# CM4_Conn.net
KiCad netlist of a schematic drawn in Altium Designer
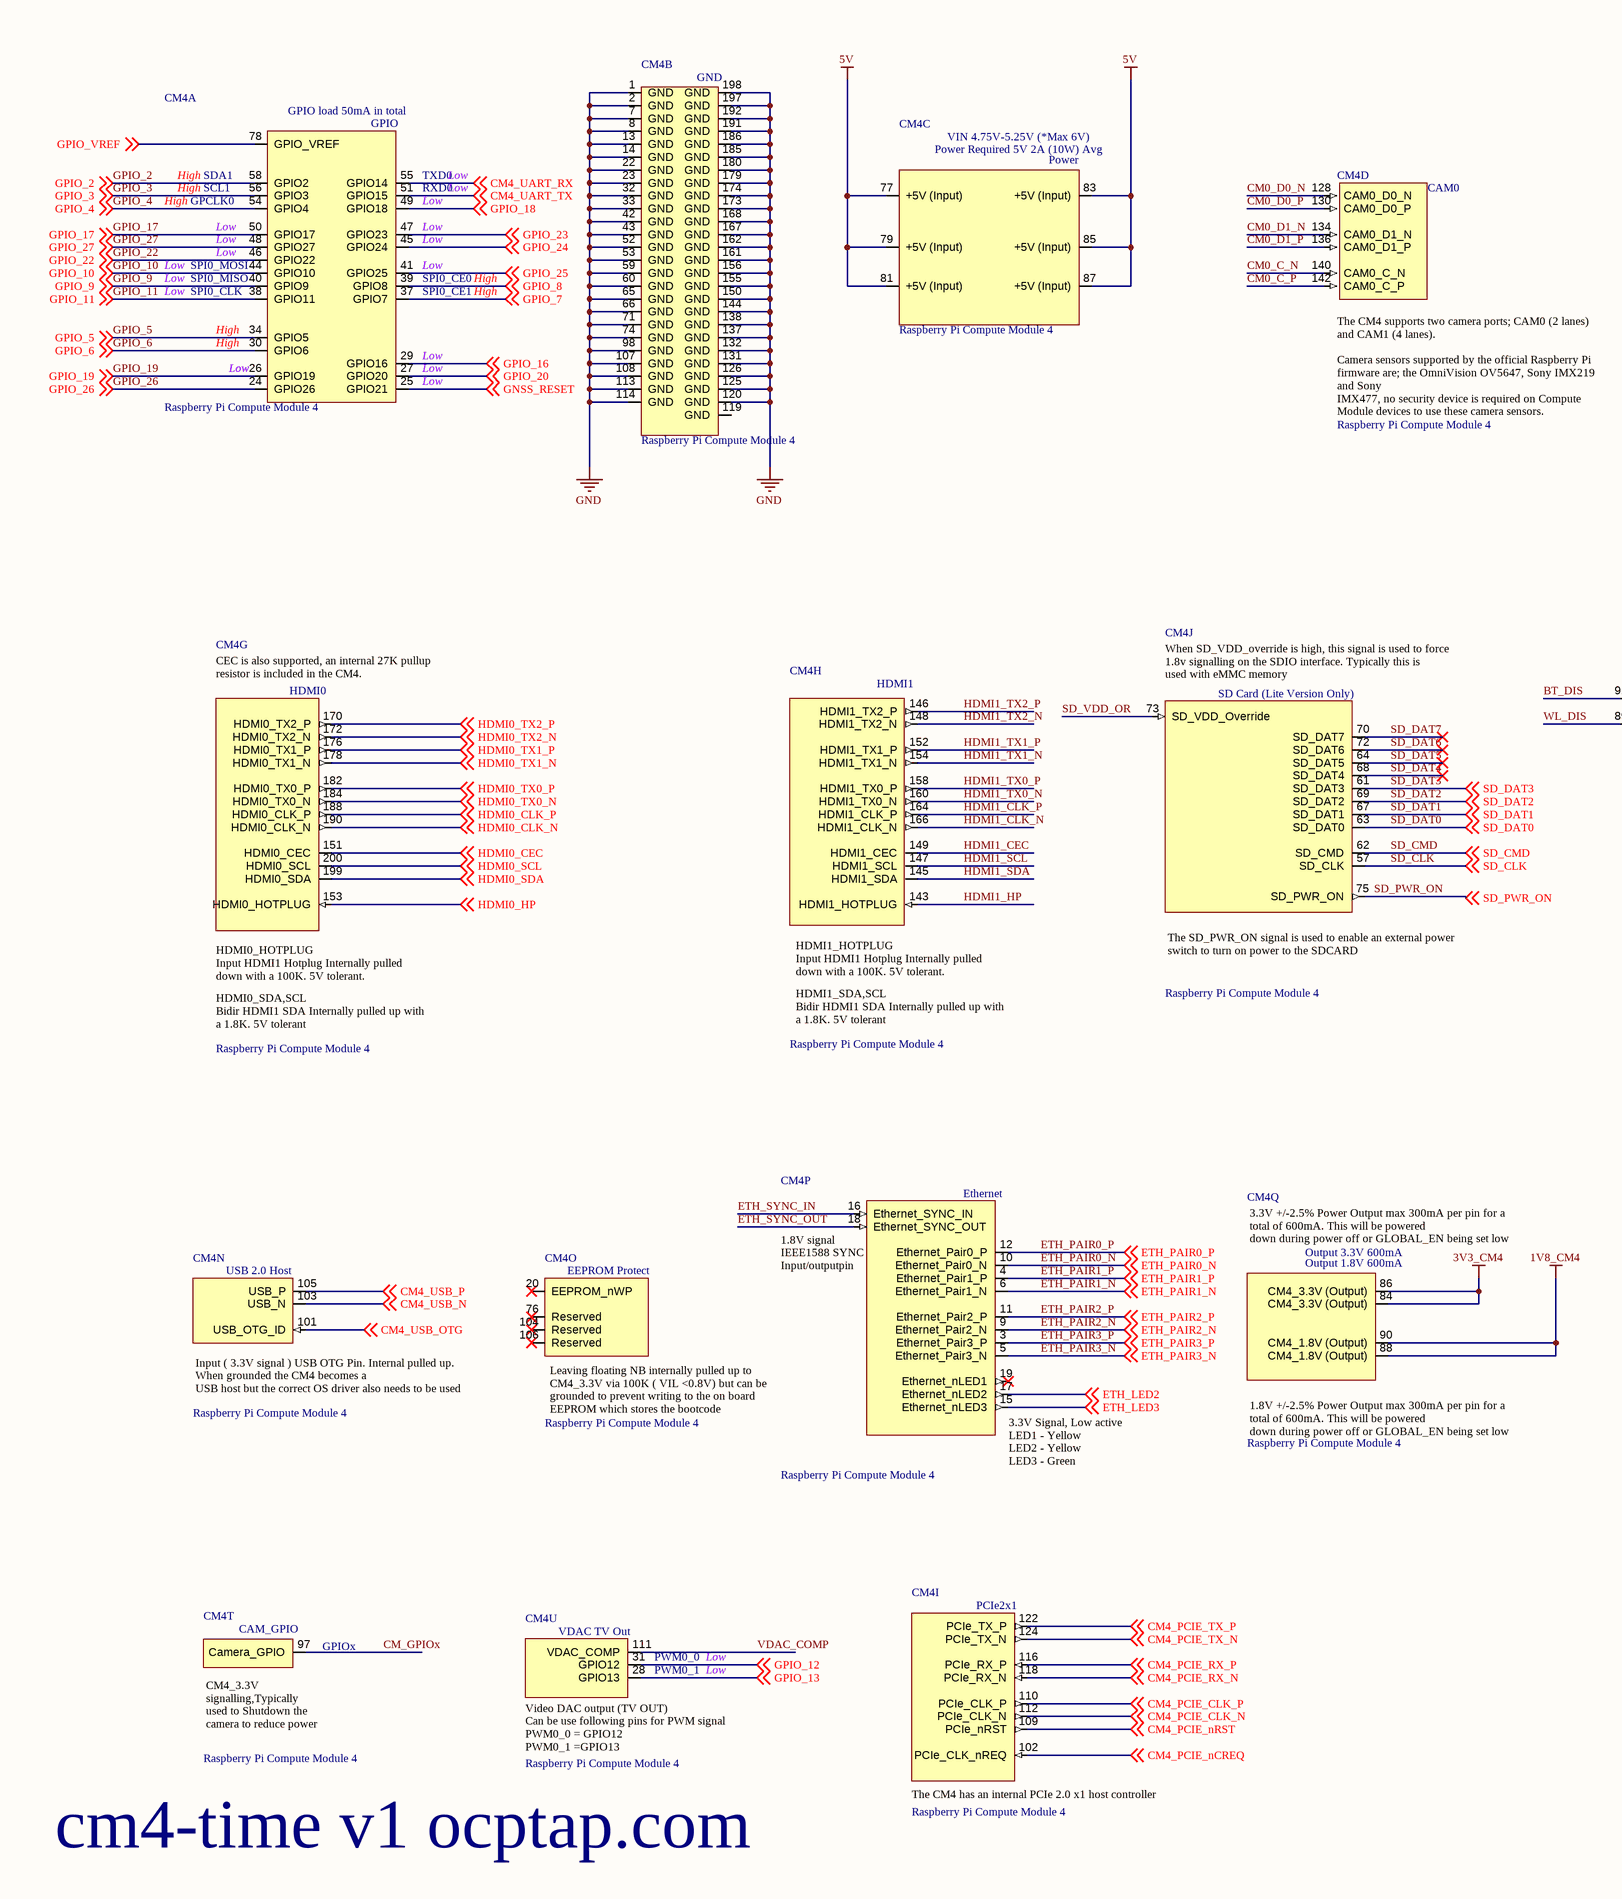
[diagram p0: CM4_Conn.SchDoc, left]
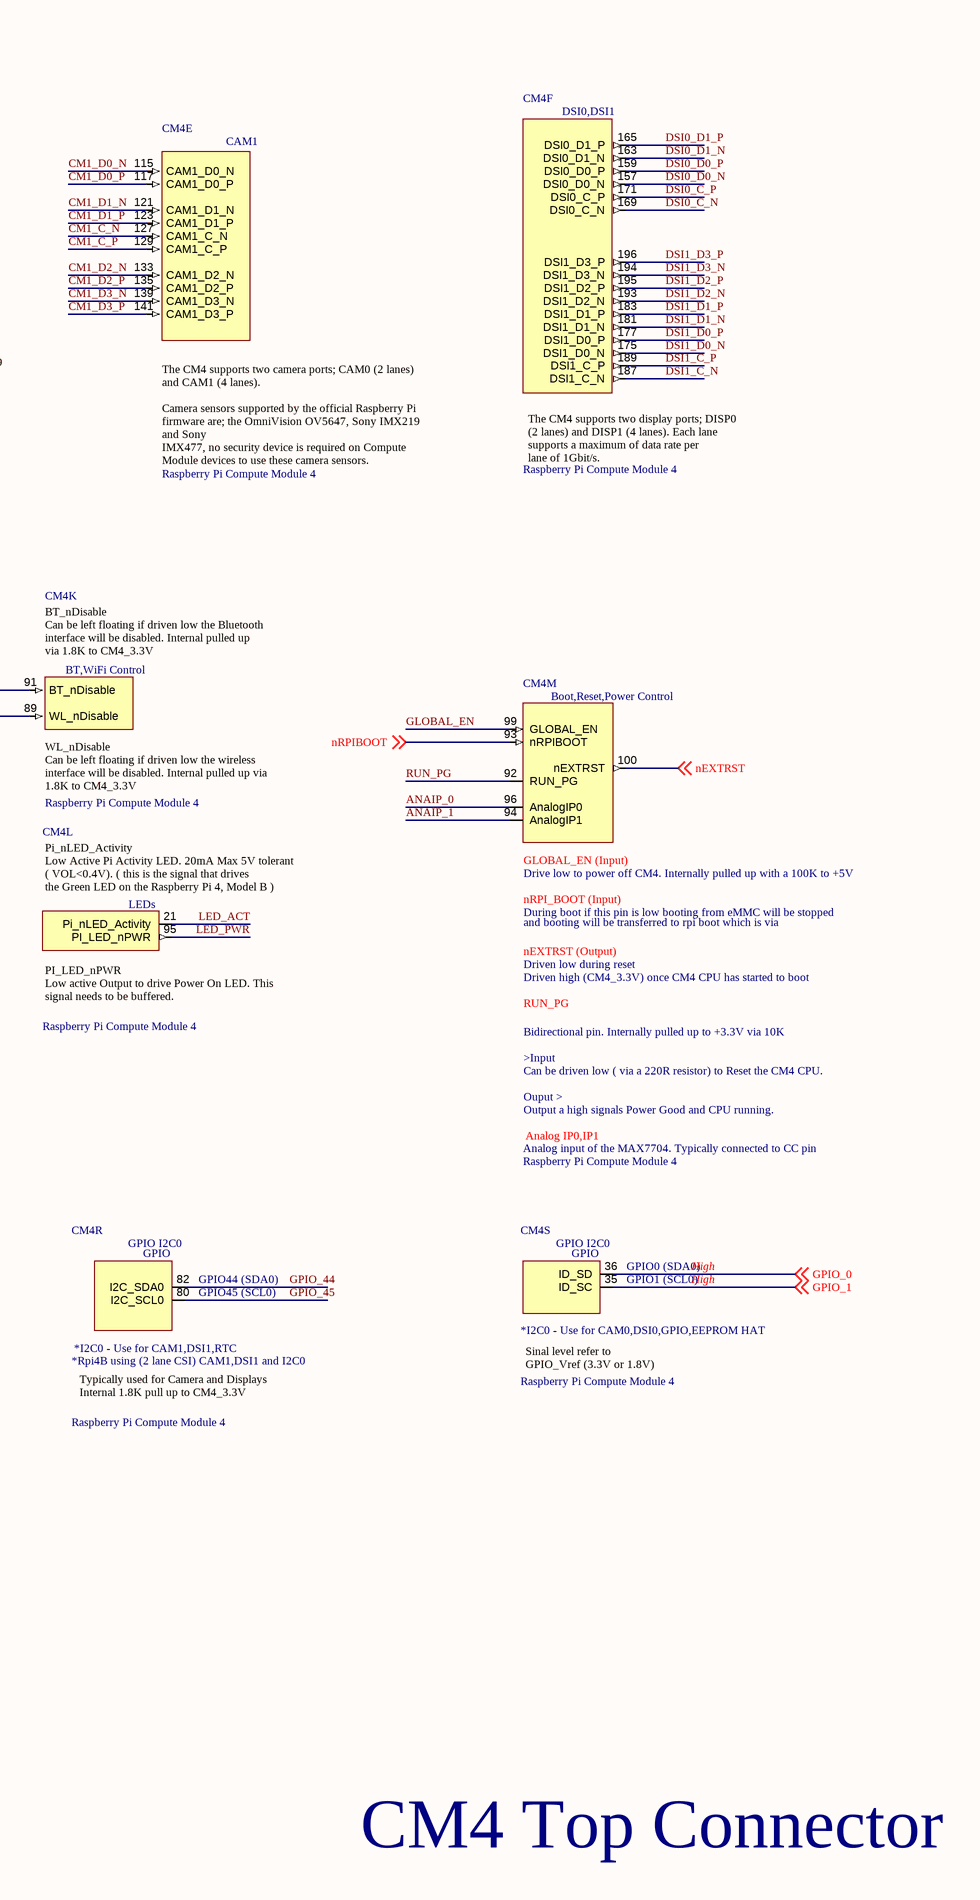
[diagram p1: CM4_Conn.SchDoc, right]

(export (version "E")
  (design (tool "Eeschema 10.0.6"))
  (components
    (comp (ref "CM4")
      (value "Raspberry Pi Compute Module 4")
      (footprint "CM4-F40C-100DS-0.4v_1.5mm_0mm")
      (description "Raspberry Pi Compute Module 4 by Amornthep Phunsin")
      (libsource (lib "CM4") (part "CM4"))
    )
  )
  (nets
    (net (code "1") (name "/ANAIP_0") (class "Default")
      (node (ref "CM4") (pin "96") (pinfunction "AnalogIP0_96") (pintype "passive"))
    )
    (net (code "2") (name "/ANAIP_1") (class "Default")
      (node (ref "CM4") (pin "94") (pinfunction "AnalogIP1_94") (pintype "passive"))
    )
    (net (code "3") (name "/BT_DIS") (class "Default")
      (node (ref "CM4") (pin "91") (pinfunction "BT_nDisable_91") (pintype "input"))
    )
    (net (code "4") (name "/CM0_C_N") (class "Default")
      (node (ref "CM4") (pin "140") (pinfunction "CAM0_C_N_140") (pintype "input"))
    )
    (net (code "5") (name "/CM0_C_P") (class "Default")
      (node (ref "CM4") (pin "142") (pinfunction "CAM0_C_P_142") (pintype "input"))
    )
    (net (code "6") (name "/CM0_D0_N") (class "Default")
      (node (ref "CM4") (pin "128") (pinfunction "CAM0_D0_N_128") (pintype "input"))
    )
    (net (code "7") (name "/CM0_D0_P") (class "Default")
      (node (ref "CM4") (pin "130") (pinfunction "CAM0_D0_P_130") (pintype "input"))
    )
    (net (code "8") (name "/CM0_D1_N") (class "Default")
      (node (ref "CM4") (pin "134") (pinfunction "CAM0_D1_N_134") (pintype "input"))
    )
    (net (code "9") (name "/CM0_D1_P") (class "Default")
      (node (ref "CM4") (pin "136") (pinfunction "CAM0_D1_P_136") (pintype "input"))
    )
    (net (code "10") (name "/CM1_C_N") (class "Default")
      (node (ref "CM4") (pin "127") (pinfunction "CAM1_C_N_127") (pintype "input"))
    )
    (net (code "11") (name "/CM1_C_P") (class "Default")
      (node (ref "CM4") (pin "129") (pinfunction "CAM1_C_P_129") (pintype "input"))
    )
    (net (code "12") (name "/CM1_D0_N") (class "Default")
      (node (ref "CM4") (pin "115") (pinfunction "CAM1_D0_N_115") (pintype "input"))
    )
    (net (code "13") (name "/CM1_D0_P") (class "Default")
      (node (ref "CM4") (pin "117") (pinfunction "CAM1_D0_P_117") (pintype "input"))
    )
    (net (code "14") (name "/CM1_D1_N") (class "Default")
      (node (ref "CM4") (pin "121") (pinfunction "CAM1_D1_N_121") (pintype "input"))
    )
    (net (code "15") (name "/CM1_D1_P") (class "Default")
      (node (ref "CM4") (pin "123") (pinfunction "CAM1_D1_P_123") (pintype "input"))
    )
    (net (code "16") (name "/CM1_D2_N") (class "Default")
      (node (ref "CM4") (pin "133") (pinfunction "CAM1_D2_N_133") (pintype "input"))
    )
    (net (code "17") (name "/CM1_D2_P") (class "Default")
      (node (ref "CM4") (pin "135") (pinfunction "CAM1_D2_P_135") (pintype "input"))
    )
    (net (code "18") (name "/CM1_D3_N") (class "Default")
      (node (ref "CM4") (pin "139") (pinfunction "CAM1_D3_N_139") (pintype "input"))
    )
    (net (code "19") (name "/CM1_D3_P") (class "Default")
      (node (ref "CM4") (pin "141") (pinfunction "CAM1_D3_P_141") (pintype "input"))
    )
    (net (code "20") (name "/CM_GPIOx") (class "Default")
      (node (ref "CM4") (pin "97") (pinfunction "Camera_GPIO_97") (pintype "passive"))
    )
    (net (code "21") (name "/DSI0_C_N") (class "Default")
      (node (ref "CM4") (pin "169") (pinfunction "DSI0_C_N_169") (pintype "output"))
    )
    (net (code "22") (name "/DSI0_C_P") (class "Default")
      (node (ref "CM4") (pin "171") (pinfunction "DSI0_C_P_171") (pintype "output"))
    )
    (net (code "23") (name "/DSI0_D0_N") (class "Default")
      (node (ref "CM4") (pin "157") (pinfunction "DSI0_D0_N_157") (pintype "output"))
    )
    (net (code "24") (name "/DSI0_D0_P") (class "Default")
      (node (ref "CM4") (pin "159") (pinfunction "DSI0_D0_P_159") (pintype "output"))
    )
    (net (code "25") (name "/DSI0_D1_N") (class "Default")
      (node (ref "CM4") (pin "163") (pinfunction "DSI0_D1_N_163") (pintype "output"))
    )
    (net (code "26") (name "/DSI0_D1_P") (class "Default")
      (node (ref "CM4") (pin "165") (pinfunction "DSI0_D1_P_165") (pintype "output"))
    )
    (net (code "27") (name "/DSI1_C_N") (class "Default")
      (node (ref "CM4") (pin "187") (pinfunction "DSI1_C_N_187") (pintype "output"))
    )
    (net (code "28") (name "/DSI1_C_P") (class "Default")
      (node (ref "CM4") (pin "189") (pinfunction "DSI1_C_P_189") (pintype "output"))
    )
    (net (code "29") (name "/DSI1_D0_N") (class "Default")
      (node (ref "CM4") (pin "175") (pinfunction "DSI1_D0_N_175") (pintype "output"))
    )
    (net (code "30") (name "/DSI1_D0_P") (class "Default")
      (node (ref "CM4") (pin "177") (pinfunction "DSI1_D0_P_177") (pintype "output"))
    )
    (net (code "31") (name "/DSI1_D1_N") (class "Default")
      (node (ref "CM4") (pin "181") (pinfunction "DSI1_D1_N_181") (pintype "output"))
    )
    (net (code "32") (name "/DSI1_D1_P") (class "Default")
      (node (ref "CM4") (pin "183") (pinfunction "DSI1_D1_P_183") (pintype "output"))
    )
    (net (code "33") (name "/DSI1_D2_N") (class "Default")
      (node (ref "CM4") (pin "193") (pinfunction "DSI1_D2_N_193") (pintype "output"))
    )
    (net (code "34") (name "/DSI1_D2_P") (class "Default")
      (node (ref "CM4") (pin "195") (pinfunction "DSI1_D2_P_195") (pintype "output"))
    )
    (net (code "35") (name "/DSI1_D3_N") (class "Default")
      (node (ref "CM4") (pin "194") (pinfunction "DSI1_D3_N_194") (pintype "output"))
    )
    (net (code "36") (name "/DSI1_D3_P") (class "Default")
      (node (ref "CM4") (pin "196") (pinfunction "DSI1_D3_P_196") (pintype "output"))
    )
    (net (code "37") (name "/ETH_SYNC_IN") (class "Default")
      (node (ref "CM4") (pin "16") (pinfunction "Ethernet_SYNC_IN_16") (pintype "input"))
    )
    (net (code "38") (name "/ETH_SYNC_OUT") (class "Default")
      (node (ref "CM4") (pin "18") (pinfunction "Ethernet_SYNC_OUT_18") (pintype "input"))
    )
    (net (code "39") (name "/GLOBAL_EN") (class "Default")
      (node (ref "CM4") (pin "99") (pinfunction "GLOBAL_EN_99") (pintype "input"))
    )
    (net (code "40") (name "/GPIO_44") (class "Default")
      (node (ref "CM4") (pin "82") (pinfunction "I2C_SDA0_82") (pintype "passive"))
    )
    (net (code "41") (name "/GPIO_45") (class "Default")
      (node (ref "CM4") (pin "80") (pinfunction "I2C_SCL0_80") (pintype "passive"))
    )
    (net (code "42") (name "/HDMI1_CEC") (class "Default")
      (node (ref "CM4") (pin "149") (pinfunction "HDMI1_CEC_149") (pintype "open_collector"))
    )
    (net (code "43") (name "/HDMI1_CLK_N") (class "Default")
      (node (ref "CM4") (pin "166") (pinfunction "HDMI1_CLK_N_166") (pintype "output"))
    )
    (net (code "44") (name "/HDMI1_CLK_P") (class "Default")
      (node (ref "CM4") (pin "164") (pinfunction "HDMI1_CLK_P_164") (pintype "output"))
    )
    (net (code "45") (name "/HDMI1_HP") (class "Default")
      (node (ref "CM4") (pin "143") (pinfunction "HDMI1_HOTPLUG_143") (pintype "input"))
    )
    (net (code "46") (name "/HDMI1_SCL") (class "Default")
      (node (ref "CM4") (pin "147") (pinfunction "HDMI1_SCL_147") (pintype "open_collector"))
    )
    (net (code "47") (name "/HDMI1_SDA") (class "Default")
      (node (ref "CM4") (pin "145") (pinfunction "HDMI1_SDA_145") (pintype "bidirectional"))
    )
    (net (code "48") (name "/HDMI1_TX0_N") (class "Default")
      (node (ref "CM4") (pin "160") (pinfunction "HDMI1_TX0_N_160") (pintype "output"))
    )
    (net (code "49") (name "/HDMI1_TX0_P") (class "Default")
      (node (ref "CM4") (pin "158") (pinfunction "HDMI1_TX0_P_158") (pintype "output"))
    )
    (net (code "50") (name "/HDMI1_TX1_N") (class "Default")
      (node (ref "CM4") (pin "154") (pinfunction "HDMI1_TX1_N_154") (pintype "output"))
    )
    (net (code "51") (name "/HDMI1_TX1_P") (class "Default")
      (node (ref "CM4") (pin "152") (pinfunction "HDMI1_TX1_P_152") (pintype "output"))
    )
    (net (code "52") (name "/HDMI1_TX2_N") (class "Default")
      (node (ref "CM4") (pin "148") (pinfunction "HDMI1_TX2_N_148") (pintype "output"))
    )
    (net (code "53") (name "/HDMI1_TX2_P") (class "Default")
      (node (ref "CM4") (pin "146") (pinfunction "HDMI1_TX2_P_146") (pintype "output"))
    )
    (net (code "54") (name "/LED_ACT") (class "Default")
      (node (ref "CM4") (pin "21") (pinfunction "Pi_nLED_Activity_21") (pintype "open_collector"))
    )
    (net (code "55") (name "/LED_PWR") (class "Default")
      (node (ref "CM4") (pin "95") (pinfunction "PI_LED_nPWR_95") (pintype "output"))
    )
    (net (code "56") (name "/RUN_PG") (class "Default")
      (node (ref "CM4") (pin "92") (pinfunction "RUN_PG_92") (pintype "passive"))
    )
    (net (code "57") (name "/SD_DAT4") (class "Default")
      (node (ref "CM4") (pin "68") (pinfunction "SD_DAT4_68") (pintype "passive+no_connect"))
    )
    (net (code "58") (name "/SD_DAT5") (class "Default")
      (node (ref "CM4") (pin "64") (pinfunction "SD_DAT5_64") (pintype "passive+no_connect"))
    )
    (net (code "59") (name "/SD_DAT6") (class "Default")
      (node (ref "CM4") (pin "72") (pinfunction "SD_DAT6_72") (pintype "passive+no_connect"))
    )
    (net (code "60") (name "/SD_DAT7") (class "Default")
      (node (ref "CM4") (pin "70") (pinfunction "SD_DAT7_70") (pintype "passive+no_connect"))
    )
    (net (code "61") (name "/SD_VDD_OR") (class "Default")
      (node (ref "CM4") (pin "73") (pinfunction "SD_VDD_Override_73") (pintype "input"))
    )
    (net (code "62") (name "/VDAC_COMP") (class "Default")
      (node (ref "CM4") (pin "111") (pinfunction "VDAC_COMP_111") (pintype "passive"))
    )
    (net (code "63") (name "/WL_DIS") (class "Default")
      (node (ref "CM4") (pin "89") (pinfunction "WL_nDisable_89") (pintype "input"))
    )
    (net (code "64") (name "1V8_CM4") (class "Default")
      (node (ref "CM4") (pin "88") (pinfunction "CM4_1.8V_(Output)_88") (pintype "power_in"))
      (node (ref "CM4") (pin "90") (pinfunction "CM4_1.8V_(Output)_90") (pintype "power_in"))
    )
    (net (code "65") (name "3V3_CM4") (class "Default")
      (node (ref "CM4") (pin "84") (pinfunction "CM4_3.3V_(Output)_84") (pintype "power_in"))
      (node (ref "CM4") (pin "86") (pinfunction "CM4_3.3V_(Output)_86") (pintype "power_in"))
    )
    (net (code "66") (name "5V") (class "Default")
      (node (ref "CM4") (pin "77") (pinfunction "+5V_(Input)_77") (pintype "power_in"))
      (node (ref "CM4") (pin "79") (pinfunction "+5V_(Input)_79") (pintype "power_in"))
      (node (ref "CM4") (pin "81") (pinfunction "+5V_(Input)_81") (pintype "power_in"))
      (node (ref "CM4") (pin "83") (pinfunction "+5V_(Input)_83") (pintype "power_in"))
      (node (ref "CM4") (pin "85") (pinfunction "+5V_(Input)_85") (pintype "power_in"))
      (node (ref "CM4") (pin "87") (pinfunction "+5V_(Input)_87") (pintype "power_in"))
    )
    (net (code "67") (name "CM4_PCIE_CLK_N") (class "Default")
      (node (ref "CM4") (pin "112") (pinfunction "PCIe_CLK_N_112") (pintype "output"))
    )
    (net (code "68") (name "CM4_PCIE_CLK_P") (class "Default")
      (node (ref "CM4") (pin "110") (pinfunction "PCIe_CLK_P_110") (pintype "output"))
    )
    (net (code "69") (name "CM4_PCIE_RX_N") (class "Default")
      (node (ref "CM4") (pin "118") (pinfunction "PCIe_RX_N_118") (pintype "input"))
    )
    (net (code "70") (name "CM4_PCIE_RX_P") (class "Default")
      (node (ref "CM4") (pin "116") (pinfunction "PCIe_RX_P_116") (pintype "input"))
    )
    (net (code "71") (name "CM4_PCIE_TX_N") (class "Default")
      (node (ref "CM4") (pin "124") (pinfunction "PCIe_TX_N_124") (pintype "output"))
    )
    (net (code "72") (name "CM4_PCIE_TX_P") (class "Default")
      (node (ref "CM4") (pin "122") (pinfunction "PCIe_TX_P_122") (pintype "output"))
    )
    (net (code "73") (name "CM4_PCIE_nCREQ") (class "Default")
      (node (ref "CM4") (pin "102") (pinfunction "PCIe_CLK_nREQ_102") (pintype "input"))
    )
    (net (code "74") (name "CM4_PCIE_nRST") (class "Default")
      (node (ref "CM4") (pin "109") (pinfunction "PCIe_nRST_109") (pintype "output"))
    )
    (net (code "75") (name "CM4_UART_RX") (class "Default")
      (node (ref "CM4") (pin "55") (pinfunction "GPIO14_55") (pintype "passive"))
    )
    (net (code "76") (name "CM4_UART_TX") (class "Default")
      (node (ref "CM4") (pin "51") (pinfunction "GPIO15_51") (pintype "passive"))
    )
    (net (code "77") (name "CM4_USB_N") (class "Default")
      (node (ref "CM4") (pin "103") (pinfunction "USB_N_103") (pintype "passive"))
    )
    (net (code "78") (name "CM4_USB_OTG") (class "Default")
      (node (ref "CM4") (pin "101") (pinfunction "USB_OTG_ID_101") (pintype "input"))
    )
    (net (code "79") (name "CM4_USB_P") (class "Default")
      (node (ref "CM4") (pin "105") (pinfunction "USB_P_105") (pintype "passive"))
    )
    (net (code "80") (name "ETH_LED2") (class "Default")
      (node (ref "CM4") (pin "17") (pinfunction "Ethernet_nLED2_17") (pintype "output"))
    )
    (net (code "81") (name "ETH_LED3") (class "Default")
      (node (ref "CM4") (pin "15") (pinfunction "Ethernet_nLED3_15") (pintype "output"))
    )
    (net (code "82") (name "ETH_PAIR0_N") (class "Default")
      (node (ref "CM4") (pin "10") (pinfunction "Ethernet_Pair0_N_10") (pintype "passive"))
    )
    (net (code "83") (name "ETH_PAIR0_P") (class "Default")
      (node (ref "CM4") (pin "12") (pinfunction "Ethernet_Pair0_P_12") (pintype "passive"))
    )
    (net (code "84") (name "ETH_PAIR1_N") (class "Default")
      (node (ref "CM4") (pin "6") (pinfunction "Ethernet_Pair1_N_6") (pintype "passive"))
    )
    (net (code "85") (name "ETH_PAIR1_P") (class "Default")
      (node (ref "CM4") (pin "4") (pinfunction "Ethernet_Pair1_P_4") (pintype "passive"))
    )
    (net (code "86") (name "ETH_PAIR2_N") (class "Default")
      (node (ref "CM4") (pin "9") (pinfunction "Ethernet_Pair2_N_9") (pintype "passive"))
    )
    (net (code "87") (name "ETH_PAIR2_P") (class "Default")
      (node (ref "CM4") (pin "11") (pinfunction "Ethernet_Pair2_P_11") (pintype "passive"))
    )
    (net (code "88") (name "ETH_PAIR3_N") (class "Default")
      (node (ref "CM4") (pin "5") (pinfunction "Ethernet_Pair3_N_5") (pintype "passive"))
    )
    (net (code "89") (name "ETH_PAIR3_P") (class "Default")
      (node (ref "CM4") (pin "3") (pinfunction "Ethernet_Pair3_P_3") (pintype "passive"))
    )
    (net (code "90") (name "GND") (class "Default")
      (node (ref "CM4") (pin "1") (pinfunction "GND_1") (pintype "power_in"))
      (node (ref "CM4") (pin "107") (pinfunction "GND_107") (pintype "power_in"))
      (node (ref "CM4") (pin "108") (pinfunction "GND_108") (pintype "power_in"))
      (node (ref "CM4") (pin "113") (pinfunction "GND_113") (pintype "power_in"))
      (node (ref "CM4") (pin "114") (pinfunction "GND_114") (pintype "power_in"))
      (node (ref "CM4") (pin "120") (pinfunction "GND_120") (pintype "power_in"))
      (node (ref "CM4") (pin "125") (pinfunction "GND_125") (pintype "power_in"))
      (node (ref "CM4") (pin "126") (pinfunction "GND_126") (pintype "power_in"))
      (node (ref "CM4") (pin "13") (pinfunction "GND_13") (pintype "power_in"))
      (node (ref "CM4") (pin "131") (pinfunction "GND_131") (pintype "power_in"))
      (node (ref "CM4") (pin "132") (pinfunction "GND_132") (pintype "power_in"))
      (node (ref "CM4") (pin "137") (pinfunction "GND_137") (pintype "power_in"))
      (node (ref "CM4") (pin "138") (pinfunction "GND_138") (pintype "power_in"))
      (node (ref "CM4") (pin "14") (pinfunction "GND_14") (pintype "power_in"))
      (node (ref "CM4") (pin "144") (pinfunction "GND_144") (pintype "power_in"))
      (node (ref "CM4") (pin "150") (pinfunction "GND_150") (pintype "power_in"))
      (node (ref "CM4") (pin "155") (pinfunction "GND_155") (pintype "power_in"))
      (node (ref "CM4") (pin "156") (pinfunction "GND_156") (pintype "power_in"))
      (node (ref "CM4") (pin "161") (pinfunction "GND_161") (pintype "power_in"))
      (node (ref "CM4") (pin "162") (pinfunction "GND_162") (pintype "power_in"))
      (node (ref "CM4") (pin "167") (pinfunction "GND_167") (pintype "power_in"))
      (node (ref "CM4") (pin "168") (pinfunction "GND_168") (pintype "power_in"))
      (node (ref "CM4") (pin "173") (pinfunction "GND_173") (pintype "power_in"))
      (node (ref "CM4") (pin "174") (pinfunction "GND_174") (pintype "power_in"))
      (node (ref "CM4") (pin "179") (pinfunction "GND_179") (pintype "power_in"))
      (node (ref "CM4") (pin "180") (pinfunction "GND_180") (pintype "power_in"))
      (node (ref "CM4") (pin "185") (pinfunction "GND_185") (pintype "power_in"))
      (node (ref "CM4") (pin "186") (pinfunction "GND_186") (pintype "power_in"))
      (node (ref "CM4") (pin "191") (pinfunction "GND_191") (pintype "power_in"))
      (node (ref "CM4") (pin "192") (pinfunction "GND_192") (pintype "power_in"))
      (node (ref "CM4") (pin "197") (pinfunction "GND_197") (pintype "power_in"))
      (node (ref "CM4") (pin "198") (pinfunction "GND_198") (pintype "power_in"))
      (node (ref "CM4") (pin "2") (pinfunction "GND_2") (pintype "power_in"))
      (node (ref "CM4") (pin "22") (pinfunction "GND_22") (pintype "power_in"))
      (node (ref "CM4") (pin "23") (pinfunction "GND_23") (pintype "power_in"))
      (node (ref "CM4") (pin "32") (pinfunction "GND_32") (pintype "power_in"))
      (node (ref "CM4") (pin "33") (pinfunction "GND_33") (pintype "power_in"))
      (node (ref "CM4") (pin "42") (pinfunction "GND_42") (pintype "power_in"))
      (node (ref "CM4") (pin "43") (pinfunction "GND_43") (pintype "power_in"))
      (node (ref "CM4") (pin "52") (pinfunction "GND_52") (pintype "power_in"))
      (node (ref "CM4") (pin "53") (pinfunction "GND_53") (pintype "power_in"))
      (node (ref "CM4") (pin "59") (pinfunction "GND_59") (pintype "power_in"))
      (node (ref "CM4") (pin "60") (pinfunction "GND_60") (pintype "power_in"))
      (node (ref "CM4") (pin "65") (pinfunction "GND_65") (pintype "power_in"))
      (node (ref "CM4") (pin "66") (pinfunction "GND_66") (pintype "power_in"))
      (node (ref "CM4") (pin "7") (pinfunction "GND_7") (pintype "power_in"))
      (node (ref "CM4") (pin "71") (pinfunction "GND_71") (pintype "power_in"))
      (node (ref "CM4") (pin "74") (pinfunction "GND_74") (pintype "power_in"))
      (node (ref "CM4") (pin "8") (pinfunction "GND_8") (pintype "power_in"))
      (node (ref "CM4") (pin "98") (pinfunction "GND_98") (pintype "power_in"))
    )
    (net (code "91") (name "GNSS_RESET") (class "Default")
      (node (ref "CM4") (pin "25") (pinfunction "GPIO21_25") (pintype "passive"))
    )
    (net (code "92") (name "GPIO_0") (class "Default")
      (node (ref "CM4") (pin "36") (pinfunction "ID_SD_36") (pintype "passive"))
    )
    (net (code "93") (name "GPIO_1") (class "Default")
      (node (ref "CM4") (pin "35") (pinfunction "ID_SC_35") (pintype "passive"))
    )
    (net (code "94") (name "GPIO_2") (class "Default")
      (node (ref "CM4") (pin "58") (pinfunction "GPIO2_58") (pintype "passive"))
    )
    (net (code "95") (name "GPIO_3") (class "Default")
      (node (ref "CM4") (pin "56") (pinfunction "GPIO3_56") (pintype "passive"))
    )
    (net (code "96") (name "GPIO_4") (class "Default")
      (node (ref "CM4") (pin "54") (pinfunction "GPIO4_54") (pintype "passive"))
    )
    (net (code "97") (name "GPIO_5") (class "Default")
      (node (ref "CM4") (pin "34") (pinfunction "GPIO5_34") (pintype "passive"))
    )
    (net (code "98") (name "GPIO_6") (class "Default")
      (node (ref "CM4") (pin "30") (pinfunction "GPIO6_30") (pintype "passive"))
    )
    (net (code "99") (name "GPIO_7") (class "Default")
      (node (ref "CM4") (pin "37") (pinfunction "GPIO7_37") (pintype "passive"))
    )
    (net (code "100") (name "GPIO_8") (class "Default")
      (node (ref "CM4") (pin "39") (pinfunction "GPIO8_39") (pintype "passive"))
    )
    (net (code "101") (name "GPIO_9") (class "Default")
      (node (ref "CM4") (pin "40") (pinfunction "GPIO9_40") (pintype "passive"))
    )
    (net (code "102") (name "GPIO_10") (class "Default")
      (node (ref "CM4") (pin "44") (pinfunction "GPIO10_44") (pintype "passive"))
    )
    (net (code "103") (name "GPIO_11") (class "Default")
      (node (ref "CM4") (pin "38") (pinfunction "GPIO11_38") (pintype "passive"))
    )
    (net (code "104") (name "GPIO_12") (class "Default")
      (node (ref "CM4") (pin "31") (pinfunction "GPIO12_31") (pintype "passive"))
    )
    (net (code "105") (name "GPIO_13") (class "Default")
      (node (ref "CM4") (pin "28") (pinfunction "GPIO13_28") (pintype "passive"))
    )
    (net (code "106") (name "GPIO_16") (class "Default")
      (node (ref "CM4") (pin "29") (pinfunction "GPIO16_29") (pintype "passive"))
    )
    (net (code "107") (name "GPIO_17") (class "Default")
      (node (ref "CM4") (pin "50") (pinfunction "GPIO17_50") (pintype "passive"))
    )
    (net (code "108") (name "GPIO_18") (class "Default")
      (node (ref "CM4") (pin "49") (pinfunction "GPIO18_49") (pintype "passive"))
    )
    (net (code "109") (name "GPIO_19") (class "Default")
      (node (ref "CM4") (pin "26") (pinfunction "GPIO19_26") (pintype "passive"))
    )
    (net (code "110") (name "GPIO_20") (class "Default")
      (node (ref "CM4") (pin "27") (pinfunction "GPIO20_27") (pintype "passive"))
    )
    (net (code "111") (name "GPIO_22") (class "Default")
      (node (ref "CM4") (pin "46") (pinfunction "GPIO22_46") (pintype "passive"))
    )
    (net (code "112") (name "GPIO_23") (class "Default")
      (node (ref "CM4") (pin "47") (pinfunction "GPIO23_47") (pintype "passive"))
    )
    (net (code "113") (name "GPIO_24") (class "Default")
      (node (ref "CM4") (pin "45") (pinfunction "GPIO24_45") (pintype "passive"))
    )
    (net (code "114") (name "GPIO_25") (class "Default")
      (node (ref "CM4") (pin "41") (pinfunction "GPIO25_41") (pintype "passive"))
    )
    (net (code "115") (name "GPIO_26") (class "Default")
      (node (ref "CM4") (pin "24") (pinfunction "GPIO26_24") (pintype "passive"))
    )
    (net (code "116") (name "GPIO_27") (class "Default")
      (node (ref "CM4") (pin "48") (pinfunction "GPIO27_48") (pintype "passive"))
    )
    (net (code "117") (name "GPIO_VREF") (class "Default")
      (node (ref "CM4") (pin "78") (pinfunction "GPIO_VREF_78") (pintype "power_in"))
    )
    (net (code "118") (name "HDMI0_CEC") (class "Default")
      (node (ref "CM4") (pin "151") (pinfunction "HDMI0_CEC_151") (pintype "open_collector"))
    )
    (net (code "119") (name "HDMI0_CLK_N") (class "Default")
      (node (ref "CM4") (pin "190") (pinfunction "HDMI0_CLK_N_190") (pintype "output"))
    )
    (net (code "120") (name "HDMI0_CLK_P") (class "Default")
      (node (ref "CM4") (pin "188") (pinfunction "HDMI0_CLK_P_188") (pintype "output"))
    )
    (net (code "121") (name "HDMI0_HP") (class "Default")
      (node (ref "CM4") (pin "153") (pinfunction "HDMI0_HOTPLUG_153") (pintype "input"))
    )
    (net (code "122") (name "HDMI0_SCL") (class "Default")
      (node (ref "CM4") (pin "200") (pinfunction "HDMI0_SCL_200") (pintype "open_collector"))
    )
    (net (code "123") (name "HDMI0_SDA") (class "Default")
      (node (ref "CM4") (pin "199") (pinfunction "HDMI0_SDA_199") (pintype "bidirectional"))
    )
    (net (code "124") (name "HDMI0_TX0_N") (class "Default")
      (node (ref "CM4") (pin "184") (pinfunction "HDMI0_TX0_N_184") (pintype "output"))
    )
    (net (code "125") (name "HDMI0_TX0_P") (class "Default")
      (node (ref "CM4") (pin "182") (pinfunction "HDMI0_TX0_P_182") (pintype "output"))
    )
    (net (code "126") (name "HDMI0_TX1_N") (class "Default")
      (node (ref "CM4") (pin "178") (pinfunction "HDMI0_TX1_N_178") (pintype "output"))
    )
    (net (code "127") (name "HDMI0_TX1_P") (class "Default")
      (node (ref "CM4") (pin "176") (pinfunction "HDMI0_TX1_P_176") (pintype "output"))
    )
    (net (code "128") (name "HDMI0_TX2_N") (class "Default")
      (node (ref "CM4") (pin "172") (pinfunction "HDMI0_TX2_N_172") (pintype "output"))
    )
    (net (code "129") (name "HDMI0_TX2_P") (class "Default")
      (node (ref "CM4") (pin "170") (pinfunction "HDMI0_TX2_P_170") (pintype "output"))
    )
    (net (code "130") (name "SD_CLK") (class "Default")
      (node (ref "CM4") (pin "57") (pinfunction "SD_CLK_57") (pintype "passive"))
    )
    (net (code "131") (name "SD_CMD") (class "Default")
      (node (ref "CM4") (pin "62") (pinfunction "SD_CMD_62") (pintype "passive"))
    )
    (net (code "132") (name "SD_DAT0") (class "Default")
      (node (ref "CM4") (pin "63") (pinfunction "SD_DAT0_63") (pintype "passive"))
    )
    (net (code "133") (name "SD_DAT1") (class "Default")
      (node (ref "CM4") (pin "67") (pinfunction "SD_DAT1_67") (pintype "passive"))
    )
    (net (code "134") (name "SD_DAT2") (class "Default")
      (node (ref "CM4") (pin "69") (pinfunction "SD_DAT2_69") (pintype "passive"))
    )
    (net (code "135") (name "SD_DAT3") (class "Default")
      (node (ref "CM4") (pin "61") (pinfunction "SD_DAT3_61") (pintype "passive"))
    )
    (net (code "136") (name "SD_PWR_ON") (class "Default")
      (node (ref "CM4") (pin "75") (pinfunction "SD_PWR_ON_75") (pintype "output"))
    )
    (net (code "137") (name "nEXTRST") (class "Default")
      (node (ref "CM4") (pin "100") (pinfunction "nEXTRST_100") (pintype "output"))
    )
    (net (code "138") (name "nRPIBOOT") (class "Default")
      (node (ref "CM4") (pin "93") (pinfunction "nRPIBOOT_93") (pintype "input"))
    )
    (net (code "139") (name "unconnected-(CM4B-GND-Pad119)") (class "Default")
      (node (ref "CM4") (pin "119") (pinfunction "GND_119") (pintype "power_in"))
    )
    (net (code "140") (name "unconnected-(CM4O-EEPROM_nWP-Pad20)") (class "Default")
      (node (ref "CM4") (pin "20") (pinfunction "EEPROM_nWP_20") (pintype "passive+no_connect"))
    )
    (net (code "141") (name "unconnected-(CM4O-Reserved-Pad76)") (class "Default")
      (node (ref "CM4") (pin "76") (pinfunction "Reserved_76") (pintype "passive+no_connect"))
    )
    (net (code "142") (name "unconnected-(CM4O-Reserved-Pad104)") (class "Default")
      (node (ref "CM4") (pin "104") (pinfunction "Reserved_104") (pintype "passive+no_connect"))
    )
    (net (code "143") (name "unconnected-(CM4O-Reserved-Pad106)") (class "Default")
      (node (ref "CM4") (pin "106") (pinfunction "Reserved_106") (pintype "passive+no_connect"))
    )
    (net (code "144") (name "unconnected-(CM4P-Ethernet_nLED1-Pad19)") (class "Default")
      (node (ref "CM4") (pin "19") (pinfunction "Ethernet_nLED1_19") (pintype "output+no_connect"))
    )
  )
)
